# Digital_DSPv3.net
KiCad netlist of a schematic drawn in Altium Designer
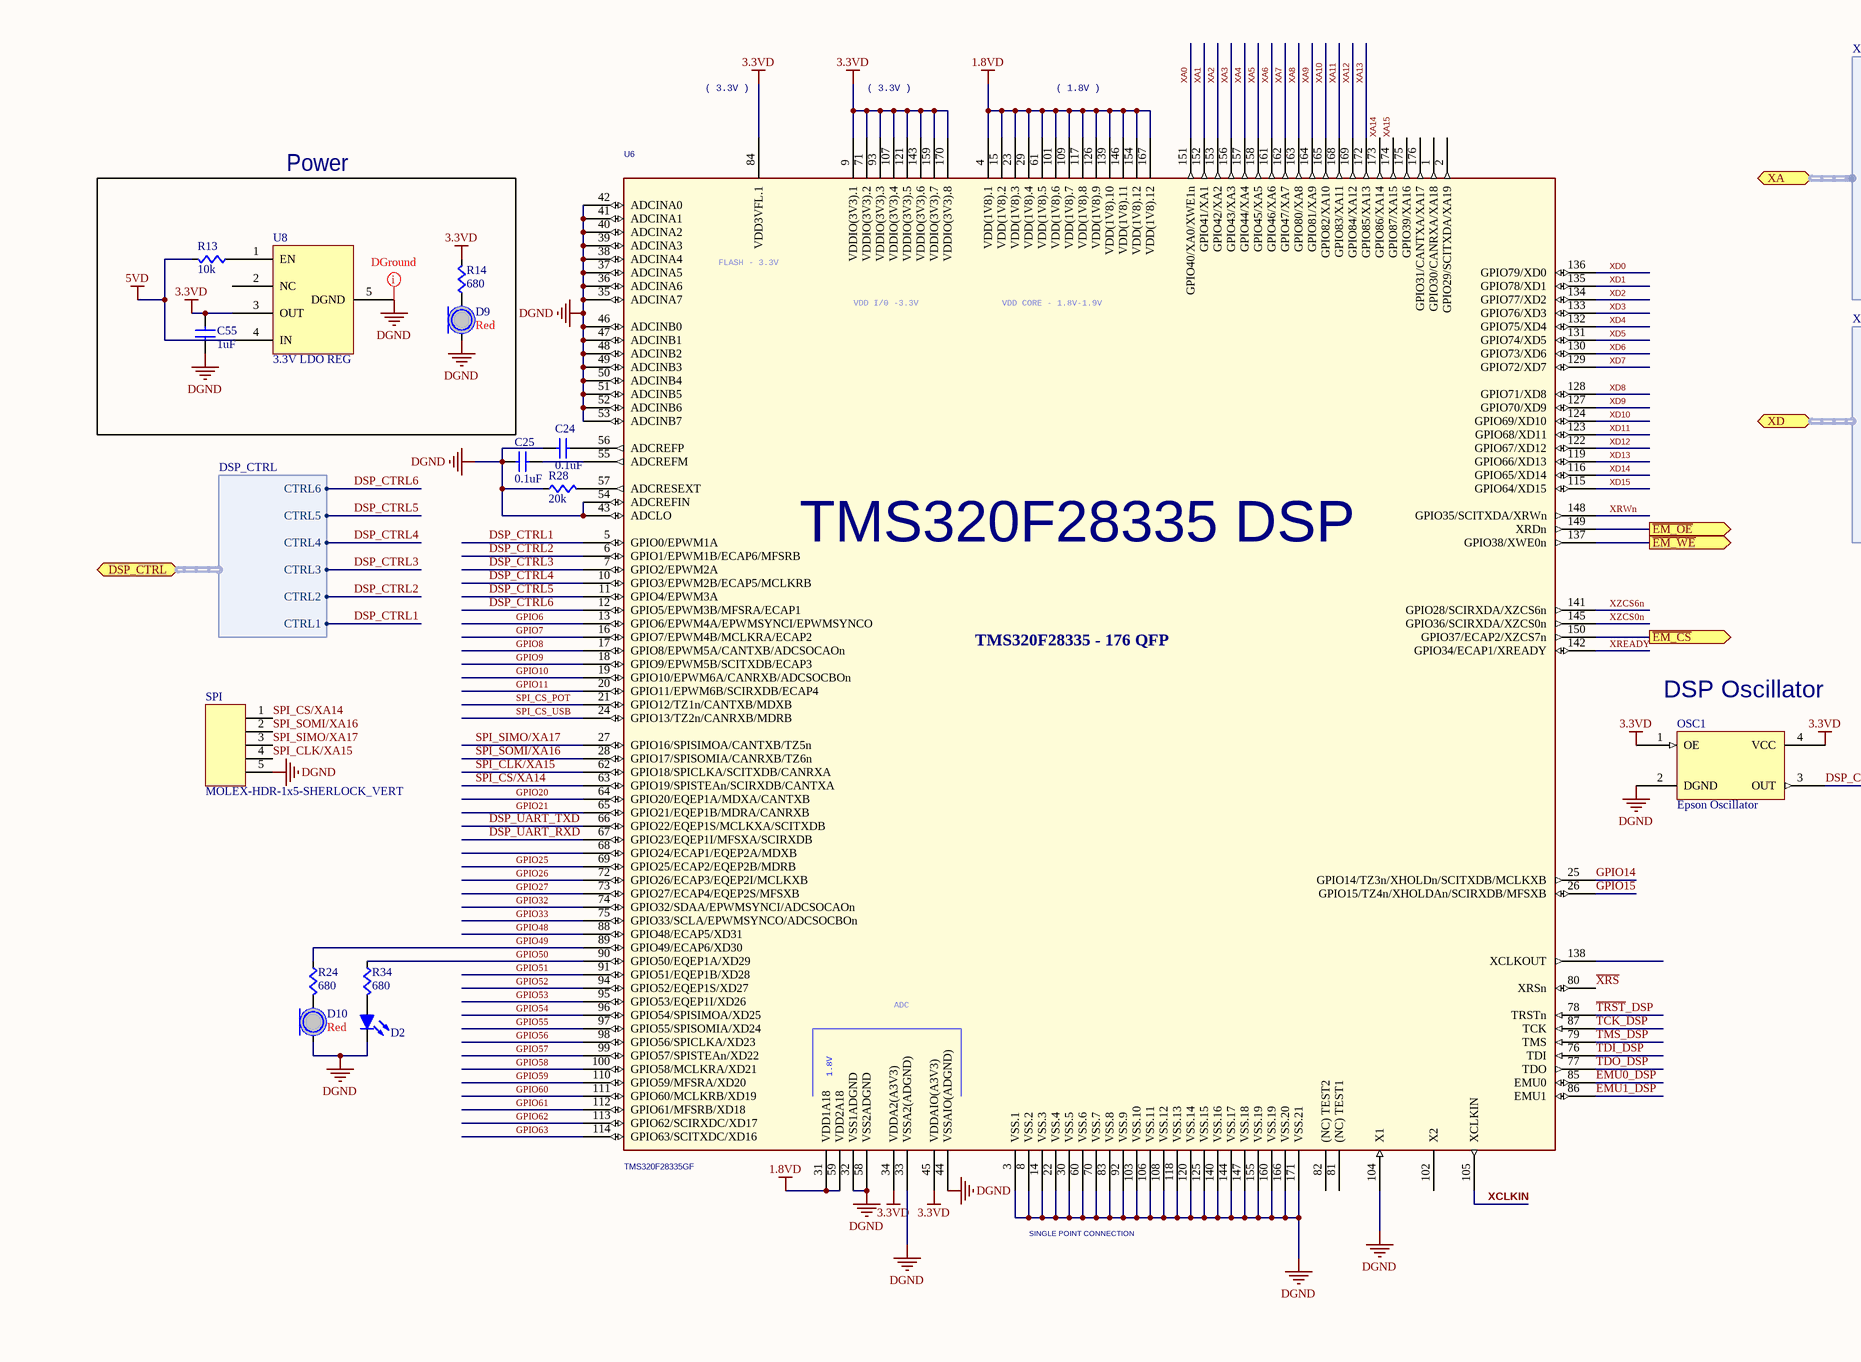
[diagram p0: Digital_DSPv3.SchDoc, top left]
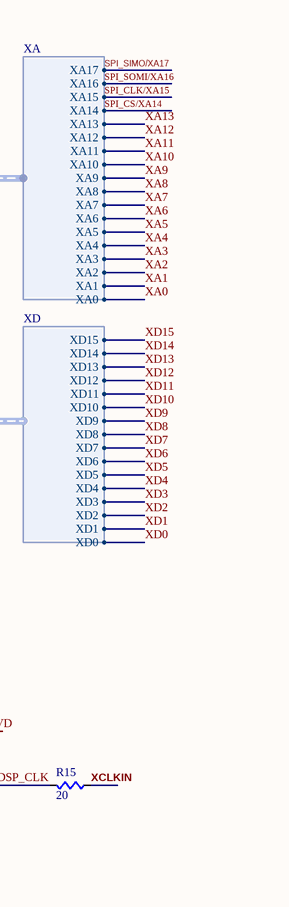
[diagram p1: Digital_DSPv3.SchDoc, top right]
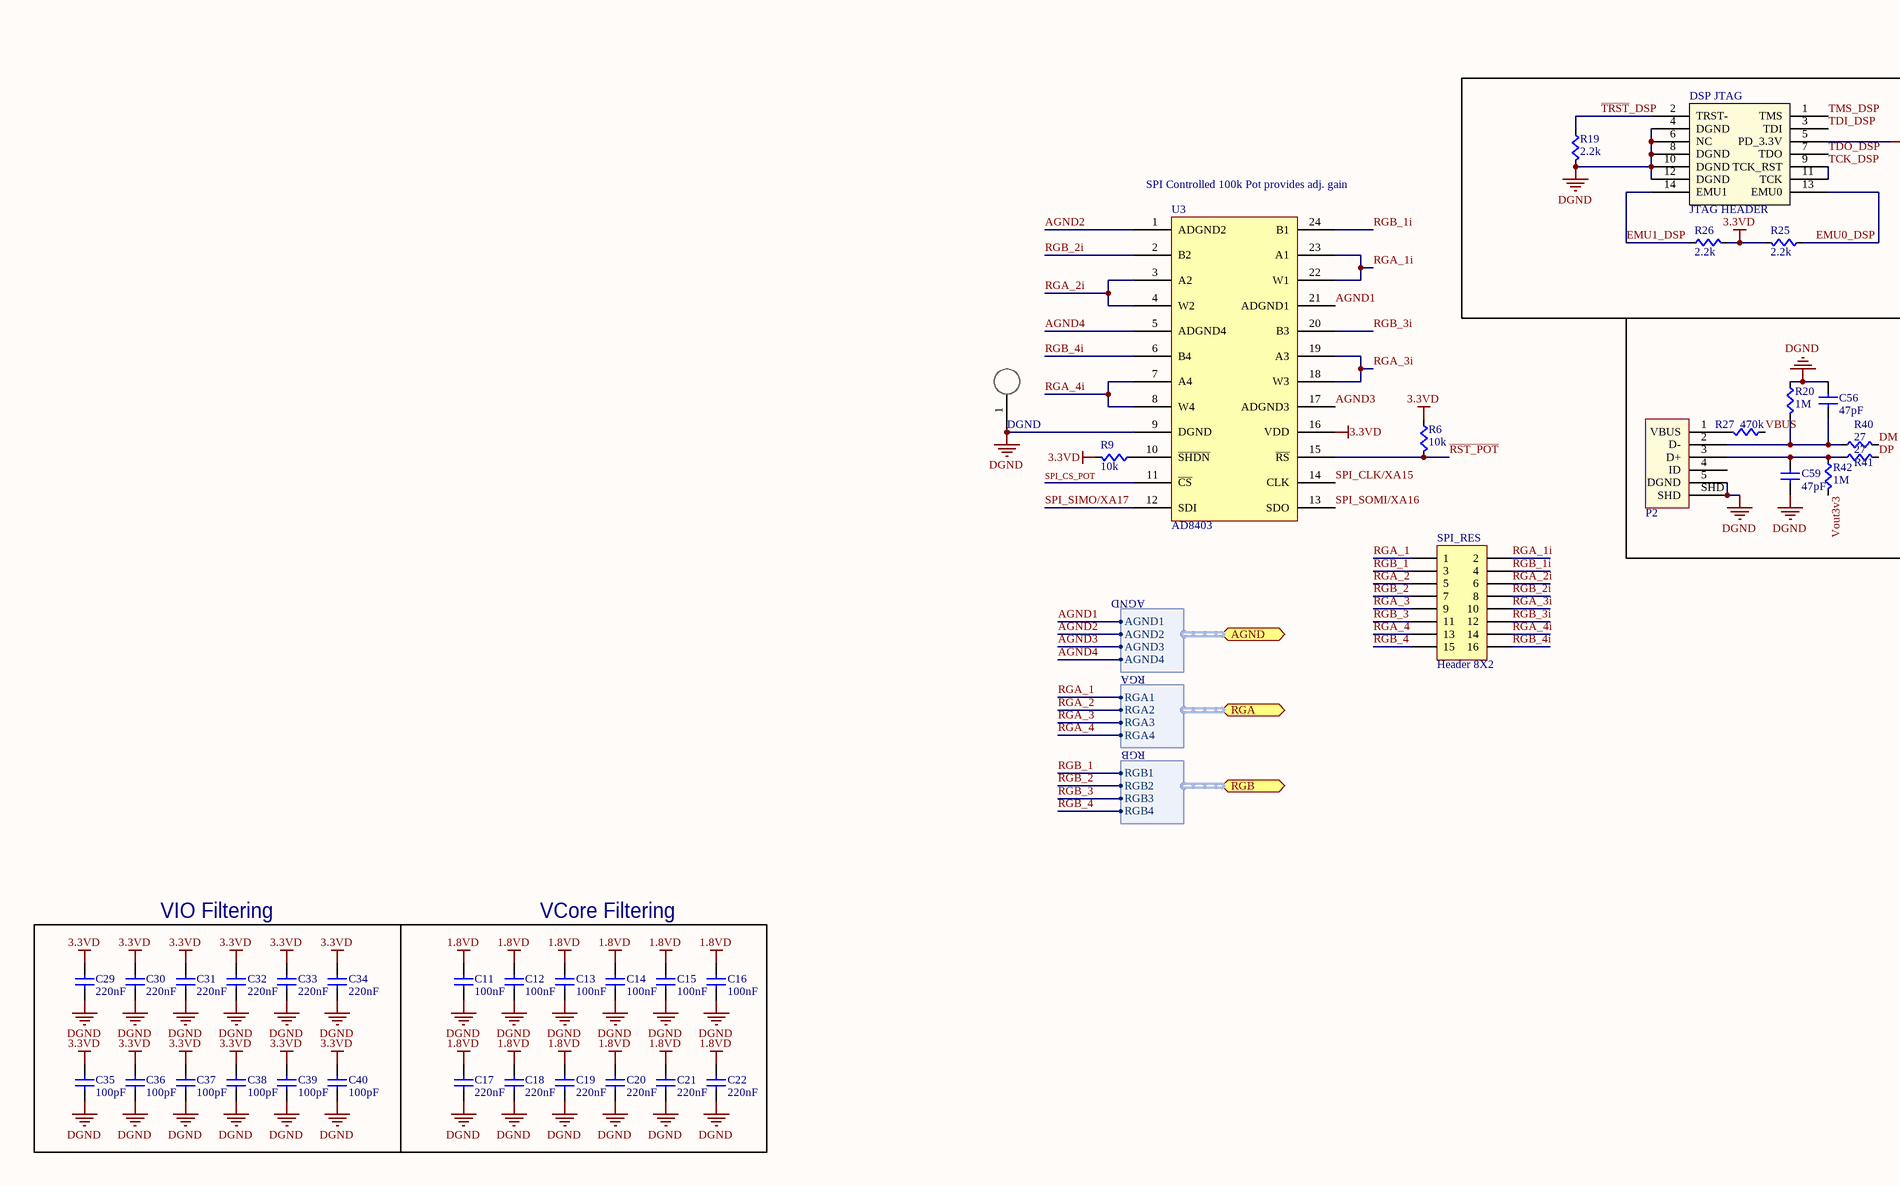
[diagram p2: Digital_DSPv3.SchDoc, bottom left]
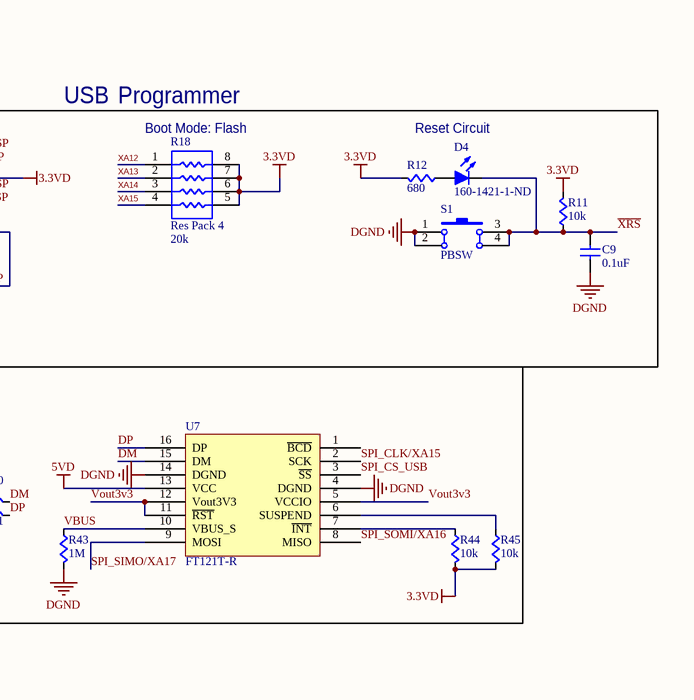
[diagram p3: Digital_DSPv3.SchDoc, bottom right]

(export (version "E")
  (design (tool "Eeschema 10.0.6"))
  (components
    (comp (ref "C9")
      (value "0.1uF")
      (footprint "CAPC0603")
      (fields (field (name "Comment") "Cap"))
      (libsource (lib "SubjuGator8") (part "Cap"))
    )
    (comp (ref "C11")
      (value "100nF")
      (footprint "CAPC0603")
      (fields (field (name "Comment") "Cap"))
      (libsource (lib "SubjuGator8") (part "Cap"))
    )
    (comp (ref "C12")
      (value "100nF")
      (footprint "CAPC0603")
      (fields (field (name "Comment") "Cap"))
      (libsource (lib "SubjuGator8") (part "Cap"))
    )
    (comp (ref "C13")
      (value "100nF")
      (footprint "CAPC0603")
      (fields (field (name "Comment") "Cap"))
      (libsource (lib "SubjuGator8") (part "Cap"))
    )
    (comp (ref "C14")
      (value "100nF")
      (footprint "CAPC0603")
      (fields (field (name "Comment") "Cap"))
      (libsource (lib "SubjuGator8") (part "Cap"))
    )
    (comp (ref "C15")
      (value "100nF")
      (footprint "CAPC0603")
      (fields (field (name "Comment") "Cap"))
      (libsource (lib "SubjuGator8") (part "Cap"))
    )
    (comp (ref "C16")
      (value "100nF")
      (footprint "CAPC0603")
      (fields (field (name "Comment") "Cap"))
      (libsource (lib "SubjuGator8") (part "Cap"))
    )
    (comp (ref "C17")
      (value "220nF")
      (footprint "CAPC0603")
      (fields (field (name "Comment") "Cap"))
      (libsource (lib "SubjuGator8") (part "Cap"))
    )
    (comp (ref "C18")
      (value "220nF")
      (footprint "CAPC0603")
      (fields (field (name "Comment") "Cap"))
      (libsource (lib "SubjuGator8") (part "Cap"))
    )
    (comp (ref "C19")
      (value "220nF")
      (footprint "CAPC0603")
      (fields (field (name "Comment") "Cap"))
      (libsource (lib "SubjuGator8") (part "Cap"))
    )
    (comp (ref "C20")
      (value "220nF")
      (footprint "CAPC0603")
      (fields (field (name "Comment") "Cap"))
      (libsource (lib "SubjuGator8") (part "Cap"))
    )
    (comp (ref "C21")
      (value "220nF")
      (footprint "CAPC0603")
      (fields (field (name "Comment") "Cap"))
      (libsource (lib "SubjuGator8") (part "Cap"))
    )
    (comp (ref "C22")
      (value "220nF")
      (footprint "CAPC0603")
      (fields (field (name "Comment") "Cap"))
      (libsource (lib "SubjuGator8") (part "Cap"))
    )
    (comp (ref "C24")
      (value "0.1uF")
      (footprint "CAPC0603")
      (description "CAP CER 1UF 50V 10% X7R 1206")
      (fields (field (name "Comment") "Cap1206"))
      (libsource (lib "Passives") (part "Cap1206"))
    )
    (comp (ref "C25")
      (value "0.1uF")
      (footprint "CAPC0603")
      (description "CAP CER 1UF 50V 10% X7R 1206")
      (fields (field (name "Comment") "Cap1206"))
      (libsource (lib "Passives") (part "Cap1206"))
    )
    (comp (ref "C29")
      (value "220nF")
      (footprint "CAPC0603")
      (fields (field (name "Comment") "Cap"))
      (libsource (lib "SubjuGator8") (part "Cap"))
    )
    (comp (ref "C30")
      (value "220nF")
      (footprint "CAPC0603")
      (fields (field (name "Comment") "Cap"))
      (libsource (lib "SubjuGator8") (part "Cap"))
    )
    (comp (ref "C31")
      (value "220nF")
      (footprint "CAPC0603")
      (fields (field (name "Comment") "Cap"))
      (libsource (lib "SubjuGator8") (part "Cap"))
    )
    (comp (ref "C32")
      (value "220nF")
      (footprint "CAPC0603")
      (fields (field (name "Comment") "Cap"))
      (libsource (lib "SubjuGator8") (part "Cap"))
    )
    (comp (ref "C33")
      (value "220nF")
      (footprint "CAPC0603")
      (fields (field (name "Comment") "Cap"))
      (libsource (lib "SubjuGator8") (part "Cap"))
    )
    (comp (ref "C34")
      (value "220nF")
      (footprint "CAPC0603")
      (fields (field (name "Comment") "Cap"))
      (libsource (lib "SubjuGator8") (part "Cap"))
    )
    (comp (ref "C35")
      (value "100pF")
      (footprint "CAPC0603")
      (fields (field (name "Comment") "Cap"))
      (libsource (lib "SubjuGator8") (part "Cap"))
    )
    (comp (ref "C36")
      (value "100pF")
      (footprint "CAPC0603")
      (fields (field (name "Comment") "Cap"))
      (libsource (lib "SubjuGator8") (part "Cap"))
    )
    (comp (ref "C37")
      (value "100pF")
      (footprint "CAPC0603")
      (fields (field (name "Comment") "Cap"))
      (libsource (lib "SubjuGator8") (part "Cap"))
    )
    (comp (ref "C38")
      (value "100pF")
      (footprint "CAPC0603")
      (fields (field (name "Comment") "Cap"))
      (libsource (lib "SubjuGator8") (part "Cap"))
    )
    (comp (ref "C39")
      (value "100pF")
      (footprint "CAPC0603")
      (fields (field (name "Comment") "Cap"))
      (libsource (lib "SubjuGator8") (part "Cap"))
    )
    (comp (ref "C40")
      (value "100pF")
      (footprint "CAPC0603")
      (fields (field (name "Comment") "Cap"))
      (libsource (lib "SubjuGator8") (part "Cap"))
    )
    (comp (ref "C55")
      (value "1uF")
      (footprint "CAPC0603")
      (description "CAP CER 1UF 50V 10% X7R 1206")
      (fields (field (name "Comment") "Cap1206"))
      (libsource (lib "Passives") (part "Cap1206"))
    )
    (comp (ref "C56")
      (value "47pF")
      (footprint "CAPC0603")
      (description "CAP CER 1UF 50V 10% X7R 1206")
      (fields (field (name "Comment") "Cap1206"))
      (libsource (lib "Passives") (part "Cap1206"))
    )
    (comp (ref "C59")
      (value "47pF")
      (footprint "CAPC0603")
      (description "CAP CER 1UF 50V 10% X7R 1206")
      (fields (field (name "Comment") "Cap1206"))
      (libsource (lib "Passives") (part "Cap1206"))
    )
    (comp (ref "D2")
      (value "LED-RED")
      (footprint "Hydrophone:LED0805-RED")
      (description "Light Emitting Diode - RED")
      (fields
        (field (name "MANUFACTURER PART NUMBER") "LTST-C171CKT")
        (field (name "MANUFACTURER") "Lite-On Inc")
      )
      (libsource (lib "Hydrophone") (part "LED-RED"))
    )
    (comp (ref "D4")
      (value "LED-RED")
      (footprint "Hydrophone:LED0805-RED")
      (description "Light Emitting Diode - RED")
      (fields
        (field (name "MANUFACTURER PART NUMBER") "LTST-C171CKT")
        (field (name "MANUFACTURER") "Lite-On Inc")
        (field (name "SUPPLIER PART NUMBER") "160-1421-1-ND")
      )
      (libsource (lib "Hydrophone") (part "LED-RED"))
    )
    (comp (ref "D9")
      (value "LED")
      (footprint "LED0805")
      (fields (field (name "COLOR") "Red"))
      (libsource (lib "SubjuGator8") (part "LED"))
    )
    (comp (ref "D10")
      (value "LED")
      (footprint "LED0805")
      (fields (field (name "COLOR") "Red"))
      (libsource (lib "SubjuGator8") (part "LED"))
    )
    (comp (ref "DGND")
      (value "Test_Point")
      (footprint "TP")
      (description "TEST POINT PC COMPACT .063\"D")
      (libsource (lib "Hydrophone") (part "Test_Point"))
    )
    (comp (ref "DSP JTAG")
      (value "JTAG HEADER")
      (footprint "Hydrophone:JTAG HEADER - 14")
      (description "14 Pin JTAG Header")
      (libsource (lib "Hydrophone") (part "JTAG-TI_14"))
    )
    (comp (ref "OSC1")
      (value "Epson Oscillator")
      (footprint "Oscillator")
      (description "15Mhz Epson Clock")
      (libsource (lib "F28335_DSC_Breakout") (part "Oscillator"))
    )
    (comp (ref "P2")
      (value "USB Micro")
      (footprint "10118192-0001LF")
      (description "USB Mini B Metal Shield SMT")
      (libsource (lib "SubjuGator8") (part "USB Micro"))
    )
    (comp (ref "R6")
      (value "10k")
      (footprint "RES0603")
      (fields (field (name "Comment") "Res"))
      (libsource (lib "SubjuGator8") (part "Res"))
    )
    (comp (ref "R9")
      (value "10k")
      (footprint "RES0603")
      (fields (field (name "Comment") "Res"))
      (libsource (lib "SubjuGator8") (part "Res"))
    )
    (comp (ref "R11")
      (value "10k")
      (footprint "RES0603")
      (fields (field (name "Comment") "Res"))
      (libsource (lib "Passives") (part "Res"))
    )
    (comp (ref "R12")
      (value "680")
      (footprint "RES0603")
      (fields (field (name "Comment") "Res"))
      (libsource (lib "SubjuGator8") (part "Res"))
    )
    (comp (ref "R13")
      (value "10k")
      (footprint "RES0603")
      (fields (field (name "Comment") "Res"))
      (libsource (lib "SubjuGator8") (part "Res"))
    )
    (comp (ref "R14")
      (value "680")
      (footprint "RES0603")
      (fields (field (name "Comment") "Res"))
      (libsource (lib "SubjuGator8") (part "Res"))
    )
    (comp (ref "R15")
      (value "20")
      (footprint "RES0603")
      (fields (field (name "Comment") "Res"))
      (libsource (lib "SubjuGator8") (part "Res"))
    )
    (comp (ref "R18")
      (value "Res Pack 4")
      (footprint "SO-8")
      (description "4 Isolated Resistor Network")
      (fields (field (name "ALTIUM_VALUE") "20k") (field (name "PUBLISHER") "Altium Limited"))
      (libsource (lib "F28335_DSC_Breakout") (part "Res Pack 4"))
    )
    (comp (ref "R19")
      (value "2.2k")
      (footprint "RES0603")
      (fields (field (name "Comment") "Res"))
      (libsource (lib "SubjuGator8") (part "Res"))
    )
    (comp (ref "R20")
      (value "1M")
      (footprint "RES0603")
      (fields (field (name "Comment") "Res"))
      (libsource (lib "SubjuGator8") (part "Res"))
    )
    (comp (ref "R24")
      (value "680")
      (footprint "RES0603")
      (fields (field (name "Comment") "Res"))
      (libsource (lib "SubjuGator8") (part "Res"))
    )
    (comp (ref "R25")
      (value "2.2k")
      (footprint "RES0603")
      (fields (field (name "Comment") "Res"))
      (libsource (lib "SubjuGator8") (part "Res"))
    )
    (comp (ref "R26")
      (value "2.2k")
      (footprint "RES0603")
      (fields (field (name "Comment") "Res"))
      (libsource (lib "SubjuGator8") (part "Res"))
    )
    (comp (ref "R27")
      (value "470k")
      (footprint "RES0603")
      (fields (field (name "Comment") "Res"))
      (libsource (lib "SubjuGator8") (part "Res"))
    )
    (comp (ref "R28")
      (value "20k")
      (footprint "RES0603")
      (fields (field (name "Comment") "Res"))
      (libsource (lib "SubjuGator8") (part "Res"))
    )
    (comp (ref "R34")
      (value "680")
      (footprint "RES0603")
      (fields (field (name "Comment") "Res"))
      (libsource (lib "SubjuGator8") (part "Res"))
    )
    (comp (ref "R40")
      (value "27")
      (footprint "RES0603")
      (fields (field (name "Comment") "Res"))
      (libsource (lib "SubjuGator8") (part "Res"))
    )
    (comp (ref "R41")
      (value "27")
      (footprint "RES0603")
      (fields (field (name "Comment") "Res"))
      (libsource (lib "SubjuGator8") (part "Res"))
    )
    (comp (ref "R42")
      (value "1M")
      (footprint "RES0603")
      (fields (field (name "Comment") "Res"))
      (libsource (lib "SubjuGator8") (part "Res"))
    )
    (comp (ref "R43")
      (value "1M")
      (footprint "RES0603")
      (fields (field (name "Comment") "Res"))
      (libsource (lib "SubjuGator8") (part "Res"))
    )
    (comp (ref "R44")
      (value "10k")
      (footprint "RES0603")
      (fields (field (name "Comment") "Res"))
      (libsource (lib "SubjuGator8") (part "Res"))
    )
    (comp (ref "R45")
      (value "10k")
      (footprint "RES0603")
      (fields (field (name "Comment") "Res"))
      (libsource (lib "SubjuGator8") (part "Res"))
    )
    (comp (ref "S1")
      (value "PBSW")
      (footprint "Hydrophone:PBSW")
      (description "Push Button Switch")
      (fields
        (field (name "MANUFACTURER") "Panasonic Electronic Components")
        (field (name "MANUFACTURER PART NUMBER") "EVQ-9P105M")
        (field (name "PUBLISHER") "Altium Limited")
      )
      (libsource (lib "Hydrophone") (part "SW-PB"))
    )
    (comp (ref "SPI")
      (value "MOLEX-HDR-1x5-SHERLOCK_VERT")
      (footprint "MOLEX-HDR-1X5-SHERLOCK-VERT")
      (libsource (lib "SubjuGator8") (part "MOLEX-HDR-1x5-SHERLOCK_VERT"))
    )
    (comp (ref "SPI_RES")
      (value "Header 8X2")
      (footprint "HDR2X8")
      (description "Header, 8-Pin, Dual row")
      (fields (field (name "PUBLISHER") "Altium Limited"))
      (libsource (lib "Miscellaneous Connectors") (part "Header 8X2"))
    )
    (comp (ref "U3")
      (value "AD8403")
      (footprint "SOIC-24n")
      (description "IC POT DGTL 8BIT 100K 4CH 24SOIC")
      (libsource (lib "SubjuGator8") (part "AD8403"))
    )
    (comp (ref "U6")
      (value "TMS320F28335GF")
      (footprint "QFP176")
      (description "Texas Instruments F28335")
      (libsource (lib "addl") (part "TMS320F283XXPGF_23"))
    )
    (comp (ref "U7")
      (value "FT121T-R")
      (footprint "TSSOP-16pin")
      (description "IC USB CONTROLLER SPI 16-TSSOP")
      (libsource (lib "SubjuGator8") (part "FT121T-R"))
    )
    (comp (ref "U8")
      (value "3.3V LDO REG")
      (footprint "SOT223-8N")
      (description "IC REG LDO 3.3V 0.5A SOT223-5")
      (libsource (lib "SubjuGator8") (part "LP38691"))
    )
  )
  (nets
    (net (code "7") (name "/AGND1") (class "Default")
      (node (ref "U3") (pin "21") (pinfunction "ADGND1_21") (pintype "passive"))
    )
    (net (code "8") (name "/AGND2") (class "Default")
      (node (ref "U3") (pin "1") (pinfunction "ADGND2_1") (pintype "passive"))
    )
    (net (code "9") (name "/AGND3") (class "Default")
      (node (ref "U3") (pin "17") (pinfunction "ADGND3_17") (pintype "passive"))
    )
    (net (code "10") (name "/AGND4") (class "Default")
      (node (ref "U3") (pin "5") (pinfunction "ADGND4_5") (pintype "passive"))
    )
    (net (code "11") (name "/DM") (class "Default")
      (node (ref "R40") (pin "1") (pinfunction "A_1") (pintype "passive"))
      (node (ref "U7") (pin "15") (pinfunction "DM_15") (pintype "passive"))
    )
    (net (code "12") (name "/DP") (class "Default")
      (node (ref "R41") (pin "1") (pinfunction "A_1") (pintype "passive"))
      (node (ref "U7") (pin "16") (pinfunction "DP_16") (pintype "passive"))
    )
    (net (code "13") (name "/DSP_CLK") (class "Default")
      (node (ref "OSC1") (pin "3") (pinfunction "OUT_3") (pintype "output"))
      (node (ref "R15") (pin "1") (pinfunction "A_1") (pintype "passive"))
    )
    (net (code "14") (name "/DSP_CTRL1") (class "Default")
      (node (ref "U6") (pin "5") (pinfunction "GPIO0/EPWM1A_5") (pintype "bidirectional"))
    )
    (net (code "15") (name "/DSP_CTRL2") (class "Default")
      (node (ref "U6") (pin "6") (pinfunction "GPIO1/EPWM1B/ECAP6/MFSRB_6") (pintype "bidirectional"))
    )
    (net (code "16") (name "/DSP_CTRL3") (class "Default")
      (node (ref "U6") (pin "7") (pinfunction "GPIO2/EPWM2A_7") (pintype "bidirectional"))
    )
    (net (code "17") (name "/DSP_CTRL4") (class "Default")
      (node (ref "U6") (pin "10") (pinfunction "GPIO3/EPWM2B/ECAP5/MCLKRB_10") (pintype "bidirectional"))
    )
    (net (code "18") (name "/DSP_CTRL5") (class "Default")
      (node (ref "U6") (pin "11") (pinfunction "GPIO4/EPWM3A_11") (pintype "bidirectional"))
    )
    (net (code "19") (name "/DSP_CTRL6") (class "Default")
      (node (ref "U6") (pin "12") (pinfunction "GPIO5/EPWM3B/MFSRA/ECAP1_12") (pintype "bidirectional"))
    )
    (net (code "20") (name "/DSP_UART_RXD") (class "Default")
      (node (ref "U6") (pin "67") (pinfunction "GPIO23/EQEP1I/MFSXA/SCIRXDB_67") (pintype "bidirectional"))
    )
    (net (code "21") (name "/DSP_UART_TXD") (class "Default")
      (node (ref "U6") (pin "66") (pinfunction "GPIO22/EQEP1S/MCLKXA/SCITXDB_66") (pintype "bidirectional"))
    )
    (net (code "22") (name "/EMU0_DSP") (class "Default")
      (node (ref "DSP JTAG") (pin "13") (pinfunction "EMU0_13") (pintype "passive"))
      (node (ref "R25") (pin "2") (pinfunction "B_2") (pintype "passive"))
      (node (ref "U6") (pin "85") (pinfunction "EMU0_85") (pintype "bidirectional"))
    )
    (net (code "23") (name "/EMU1_DSP") (class "Default")
      (node (ref "DSP JTAG") (pin "14") (pinfunction "EMU1_14") (pintype "passive"))
      (node (ref "R26") (pin "2") (pinfunction "B_2") (pintype "passive"))
      (node (ref "U6") (pin "86") (pinfunction "EMU1_86") (pintype "bidirectional"))
    )
    (net (code "24") (name "/GPIO6") (class "Default")
      (node (ref "U6") (pin "13") (pinfunction "GPIO6/EPWM4A/EPWMSYNCI/EPWMSYNCO_13") (pintype "bidirectional"))
    )
    (net (code "25") (name "/GPIO7") (class "Default")
      (node (ref "U6") (pin "16") (pinfunction "GPIO7/EPWM4B/MCLKRA/ECAP2_16") (pintype "bidirectional"))
    )
    (net (code "26") (name "/GPIO8") (class "Default")
      (node (ref "U6") (pin "17") (pinfunction "GPIO8/EPWM5A/CANTXB/ADCSOCAOn_17") (pintype "bidirectional"))
    )
    (net (code "27") (name "/GPIO9") (class "Default")
      (node (ref "U6") (pin "18") (pinfunction "GPIO9/EPWM5B/SCITXDB/ECAP3_18") (pintype "bidirectional"))
    )
    (net (code "28") (name "/GPIO10") (class "Default")
      (node (ref "U6") (pin "19") (pinfunction "GPIO10/EPWM6A/CANRXB/ADCSOCBOn_19") (pintype "bidirectional"))
    )
    (net (code "29") (name "/GPIO11") (class "Default")
      (node (ref "U6") (pin "20") (pinfunction "GPIO11/EPWM6B/SCIRXDB/ECAP4_20") (pintype "bidirectional"))
    )
    (net (code "30") (name "/GPIO14") (class "Default")
      (node (ref "U6") (pin "25") (pinfunction "GPIO14/TZ3n/XHOLDn/SCITXDB/MCLKXB_25") (pintype "output"))
    )
    (net (code "31") (name "/GPIO15") (class "Default")
      (node (ref "U6") (pin "26") (pinfunction "GPIO15/TZ4n/XHOLDAn/SCIRXDB/MFSXB_26") (pintype "bidirectional"))
    )
    (net (code "32") (name "/GPIO20") (class "Default")
      (node (ref "U6") (pin "64") (pinfunction "GPIO20/EQEP1A/MDXA/CANTXB_64") (pintype "bidirectional"))
    )
    (net (code "33") (name "/GPIO21") (class "Default")
      (node (ref "U6") (pin "65") (pinfunction "GPIO21/EQEP1B/MDRA/CANRXB_65") (pintype "bidirectional"))
    )
    (net (code "34") (name "/GPIO25") (class "Default")
      (node (ref "U6") (pin "69") (pinfunction "GPIO25/ECAP2/EQEP2B/MDRB_69") (pintype "bidirectional"))
    )
    (net (code "35") (name "/GPIO26") (class "Default")
      (node (ref "U6") (pin "72") (pinfunction "GPIO26/ECAP3/EQEP2I/MCLKXB_72") (pintype "bidirectional"))
    )
    (net (code "36") (name "/GPIO27") (class "Default")
      (node (ref "U6") (pin "73") (pinfunction "GPIO27/ECAP4/EQEP2S/MFSXB_73") (pintype "bidirectional"))
    )
    (net (code "37") (name "/GPIO32") (class "Default")
      (node (ref "U6") (pin "74") (pinfunction "GPIO32/SDAA/EPWMSYNCI/ADCSOCAOn_74") (pintype "bidirectional"))
    )
    (net (code "38") (name "/GPIO33") (class "Default")
      (node (ref "U6") (pin "75") (pinfunction "GPIO33/SCLA/EPWMSYNCO/ADCSOCBOn_75") (pintype "bidirectional"))
    )
    (net (code "39") (name "/GPIO48") (class "Default")
      (node (ref "U6") (pin "88") (pinfunction "GPIO48/ECAP5/XD31_88") (pintype "bidirectional"))
    )
    (net (code "40") (name "/GPIO49") (class "Default")
      (node (ref "R24") (pin "2") (pinfunction "B_2") (pintype "passive"))
      (node (ref "U6") (pin "89") (pinfunction "GPIO49/ECAP6/XD30_89") (pintype "bidirectional"))
    )
    (net (code "41") (name "/GPIO50") (class "Default")
      (node (ref "R34") (pin "2") (pinfunction "B_2") (pintype "passive"))
      (node (ref "U6") (pin "90") (pinfunction "GPIO50/EQEP1A/XD29_90") (pintype "bidirectional"))
    )
    (net (code "42") (name "/GPIO51") (class "Default")
      (node (ref "U6") (pin "91") (pinfunction "GPIO51/EQEP1B/XD28_91") (pintype "bidirectional"))
    )
    (net (code "43") (name "/GPIO52") (class "Default")
      (node (ref "U6") (pin "94") (pinfunction "GPIO52/EQEP1S/XD27_94") (pintype "bidirectional"))
    )
    (net (code "44") (name "/GPIO53") (class "Default")
      (node (ref "U6") (pin "95") (pinfunction "GPIO53/EQEP1I/XD26_95") (pintype "bidirectional"))
    )
    (net (code "45") (name "/GPIO54") (class "Default")
      (node (ref "U6") (pin "96") (pinfunction "GPIO54/SPISIMOA/XD25_96") (pintype "bidirectional"))
    )
    (net (code "46") (name "/GPIO55") (class "Default")
      (node (ref "U6") (pin "97") (pinfunction "GPIO55/SPISOMIA/XD24_97") (pintype "bidirectional"))
    )
    (net (code "47") (name "/GPIO56") (class "Default")
      (node (ref "U6") (pin "98") (pinfunction "GPIO56/SPICLKA/XD23_98") (pintype "bidirectional"))
    )
    (net (code "48") (name "/GPIO57") (class "Default")
      (node (ref "U6") (pin "99") (pinfunction "GPIO57/SPISTEAn/XD22_99") (pintype "bidirectional"))
    )
    (net (code "49") (name "/GPIO58") (class "Default")
      (node (ref "U6") (pin "100") (pinfunction "GPIO58/MCLKRA/XD21_100") (pintype "bidirectional"))
    )
    (net (code "50") (name "/GPIO59") (class "Default")
      (node (ref "U6") (pin "110") (pinfunction "GPIO59/MFSRA/XD20_110") (pintype "bidirectional"))
    )
    (net (code "51") (name "/GPIO60") (class "Default")
      (node (ref "U6") (pin "111") (pinfunction "GPIO60/MCLKRB/XD19_111") (pintype "bidirectional"))
    )
    (net (code "52") (name "/GPIO61") (class "Default")
      (node (ref "U6") (pin "112") (pinfunction "GPIO61/MFSRB/XD18_112") (pintype "bidirectional"))
    )
    (net (code "53") (name "/GPIO62") (class "Default")
      (node (ref "U6") (pin "113") (pinfunction "GPIO62/SCIRXDC/XD17_113") (pintype "bidirectional"))
    )
    (net (code "54") (name "/GPIO63") (class "Default")
      (node (ref "U6") (pin "114") (pinfunction "GPIO63/SCITXDC/XD16_114") (pintype "bidirectional"))
    )
    (net (code "55") (name "/RGA_1") (class "Default")
      (node (ref "SPI_RES") (pin "1") (pinfunction "1_1") (pintype "passive"))
    )
    (net (code "56") (name "/RGA_1i") (class "Default")
      (node (ref "SPI_RES") (pin "2") (pinfunction "2_2") (pintype "passive"))
      (node (ref "U3") (pin "22") (pinfunction "W1_22") (pintype "passive"))
      (node (ref "U3") (pin "23") (pinfunction "A1_23") (pintype "passive"))
    )
    (net (code "57") (name "/RGA_2") (class "Default")
      (node (ref "SPI_RES") (pin "5") (pinfunction "5_5") (pintype "passive"))
    )
    (net (code "58") (name "/RGA_2i") (class "Default")
      (node (ref "SPI_RES") (pin "6") (pinfunction "6_6") (pintype "passive"))
      (node (ref "U3") (pin "3") (pinfunction "A2_3") (pintype "passive"))
      (node (ref "U3") (pin "4") (pinfunction "W2_4") (pintype "passive"))
    )
    (net (code "59") (name "/RGA_3") (class "Default")
      (node (ref "SPI_RES") (pin "9") (pinfunction "9_9") (pintype "passive"))
    )
    (net (code "60") (name "/RGA_3i") (class "Default")
      (node (ref "SPI_RES") (pin "10") (pinfunction "10_10") (pintype "passive"))
      (node (ref "U3") (pin "18") (pinfunction "W3_18") (pintype "passive"))
      (node (ref "U3") (pin "19") (pinfunction "A3_19") (pintype "passive"))
    )
    (net (code "61") (name "/RGA_4") (class "Default")
      (node (ref "SPI_RES") (pin "13") (pinfunction "13_13") (pintype "passive"))
    )
    (net (code "62") (name "/RGA_4i") (class "Default")
      (node (ref "SPI_RES") (pin "14") (pinfunction "14_14") (pintype "passive"))
      (node (ref "U3") (pin "7") (pinfunction "A4_7") (pintype "passive"))
      (node (ref "U3") (pin "8") (pinfunction "W4_8") (pintype "passive"))
    )
    (net (code "63") (name "/RGB_1") (class "Default")
      (node (ref "SPI_RES") (pin "3") (pinfunction "3_3") (pintype "passive"))
    )
    (net (code "64") (name "/RGB_1i") (class "Default")
      (node (ref "SPI_RES") (pin "4") (pinfunction "4_4") (pintype "passive"))
      (node (ref "U3") (pin "24") (pinfunction "B1_24") (pintype "passive"))
    )
    (net (code "65") (name "/RGB_2") (class "Default")
      (node (ref "SPI_RES") (pin "7") (pinfunction "7_7") (pintype "passive"))
    )
    (net (code "66") (name "/RGB_2i") (class "Default")
      (node (ref "SPI_RES") (pin "8") (pinfunction "8_8") (pintype "passive"))
      (node (ref "U3") (pin "2") (pinfunction "B2_2") (pintype "passive"))
    )
    (net (code "67") (name "/RGB_3") (class "Default")
      (node (ref "SPI_RES") (pin "11") (pinfunction "11_11") (pintype "passive"))
    )
    (net (code "68") (name "/RGB_3i") (class "Default")
      (node (ref "SPI_RES") (pin "12") (pinfunction "12_12") (pintype "passive"))
      (node (ref "U3") (pin "20") (pinfunction "B3_20") (pintype "passive"))
    )
    (net (code "69") (name "/RGB_4") (class "Default")
      (node (ref "SPI_RES") (pin "15") (pinfunction "15_15") (pintype "passive"))
    )
    (net (code "70") (name "/RGB_4i") (class "Default")
      (node (ref "SPI_RES") (pin "16") (pinfunction "16_16") (pintype "passive"))
      (node (ref "U3") (pin "6") (pinfunction "B4_6") (pintype "passive"))
    )
    (net (code "71") (name "/SPI_CLK{slash}XA15") (class "Default")
      (node (ref "SPI") (pin "4") (pinfunction "4_4") (pintype "passive"))
      (node (ref "U3") (pin "14") (pinfunction "CLK_14") (pintype "passive"))
      (node (ref "U6") (pin "62") (pinfunction "GPIO18/SPICLKA/SCITXDB/CANRXA_62") (pintype "bidirectional"))
      (node (ref "U7") (pin "2") (pinfunction "SCK_2") (pintype "passive"))
    )
    (net (code "72") (name "/SPI_CS_POT") (class "Default")
      (node (ref "U3") (pin "11") (pinfunction "~{CS}_11") (pintype "passive"))
      (node (ref "U6") (pin "21") (pinfunction "GPIO12/TZ1n/CANTXB/MDXB_21") (pintype "bidirectional"))
    )
    (net (code "73") (name "/SPI_CS_USB") (class "Default")
      (node (ref "U6") (pin "24") (pinfunction "GPIO13/TZ2n/CANRXB/MDRB_24") (pintype "bidirectional"))
      (node (ref "U7") (pin "3") (pinfunction "~{SS}_3") (pintype "passive"))
    )
    (net (code "74") (name "/SPI_CS{slash}XA14") (class "Default")
      (node (ref "SPI") (pin "1") (pinfunction "1_1") (pintype "passive"))
      (node (ref "U6") (pin "63") (pinfunction "GPIO19/SPISTEAn/SCIRXDB/CANTXA_63") (pintype "bidirectional"))
    )
    (net (code "75") (name "/SPI_SIMO{slash}XA17") (class "Default")
      (node (ref "SPI") (pin "3") (pinfunction "3_3") (pintype "passive"))
      (node (ref "U3") (pin "12") (pinfunction "SDI_12") (pintype "passive"))
      (node (ref "U6") (pin "27") (pinfunction "GPIO16/SPISIMOA/CANTXB/TZ5n_27") (pintype "bidirectional"))
      (node (ref "U7") (pin "9") (pinfunction "MOSI_9") (pintype "passive"))
    )
    (net (code "76") (name "/SPI_SOMI{slash}XA16") (class "Default")
      (node (ref "SPI") (pin "2") (pinfunction "2_2") (pintype "passive"))
      (node (ref "U3") (pin "13") (pinfunction "SDO_13") (pintype "passive"))
      (node (ref "U6") (pin "28") (pinfunction "GPIO17/SPISOMIA/CANRXB/TZ6n_28") (pintype "bidirectional"))
      (node (ref "U7") (pin "8") (pinfunction "MISO_8") (pintype "passive"))
    )
    (net (code "77") (name "/TCK_DSP") (class "Default")
      (node (ref "DSP JTAG") (pin "11") (pinfunction "TCK_11") (pintype "passive"))
      (node (ref "DSP JTAG") (pin "9") (pinfunction "TCK_RST_9") (pintype "passive"))
      (node (ref "U6") (pin "87") (pinfunction "TCK_87") (pintype "input"))
    )
    (net (code "78") (name "/TDI_DSP") (class "Default")
      (node (ref "DSP JTAG") (pin "3") (pinfunction "TDI_3") (pintype "passive"))
      (node (ref "U6") (pin "76") (pinfunction "TDI_76") (pintype "input"))
    )
    (net (code "79") (name "/TDO_DSP") (class "Default")
      (node (ref "DSP JTAG") (pin "7") (pinfunction "TDO_7") (pintype "passive"))
      (node (ref "U6") (pin "77") (pinfunction "TDO_77") (pintype "output"))
    )
    (net (code "80") (name "/TMS_DSP") (class "Default")
      (node (ref "DSP JTAG") (pin "1") (pinfunction "TMS_1") (pintype "passive"))
      (node (ref "U6") (pin "79") (pinfunction "TMS_79") (pintype "input"))
    )
    (net (code "81") (name "/VBUS") (class "Default")
      (node (ref "R27") (pin "2") (pinfunction "B_2") (pintype "passive"))
      (node (ref "R43") (pin "2") (pinfunction "B_2") (pintype "passive"))
      (node (ref "U7") (pin "10") (pinfunction "VBUS_S_10") (pintype "passive"))
    )
    (net (code "82") (name "/Vout3v3") (class "Default")
      (node (ref "R42") (pin "1") (pinfunction "A_1") (pintype "passive"))
      (node (ref "U7") (pin "11") (pinfunction "~{RST}_11") (pintype "passive"))
      (node (ref "U7") (pin "12") (pinfunction "Vout3V3_12") (pintype "passive"))
      (node (ref "U7") (pin "5") (pinfunction "VCCIO_5") (pintype "passive"))
    )
    (net (code "83") (name "/XA0") (class "Default")
      (node (ref "U6") (pin "151") (pinfunction "GPIO40/XA0/XWE1n_151") (pintype "output"))
    )
    (net (code "84") (name "/XA1") (class "Default")
      (node (ref "U6") (pin "152") (pinfunction "GPIO41/XA1_152") (pintype "output"))
    )
    (net (code "85") (name "/XA2") (class "Default")
      (node (ref "U6") (pin "153") (pinfunction "GPIO42/XA2_153") (pintype "output"))
    )
    (net (code "86") (name "/XA3") (class "Default")
      (node (ref "U6") (pin "156") (pinfunction "GPIO43/XA3_156") (pintype "output"))
    )
    (net (code "87") (name "/XA4") (class "Default")
      (node (ref "U6") (pin "157") (pinfunction "GPIO44/XA4_157") (pintype "output"))
    )
    (net (code "88") (name "/XA5") (class "Default")
      (node (ref "U6") (pin "158") (pinfunction "GPIO45/XA5_158") (pintype "output"))
    )
    (net (code "89") (name "/XA6") (class "Default")
      (node (ref "U6") (pin "161") (pinfunction "GPIO46/XA6_161") (pintype "output"))
    )
    (net (code "90") (name "/XA7") (class "Default")
      (node (ref "U6") (pin "162") (pinfunction "GPIO47/XA7_162") (pintype "output"))
    )
    (net (code "91") (name "/XA8") (class "Default")
      (node (ref "U6") (pin "163") (pinfunction "GPIO80/XA8_163") (pintype "output"))
    )
    (net (code "92") (name "/XA9") (class "Default")
      (node (ref "U6") (pin "164") (pinfunction "GPIO81/XA9_164") (pintype "output"))
    )
    (net (code "93") (name "/XA10") (class "Default")
      (node (ref "U6") (pin "165") (pinfunction "GPIO82/XA10_165") (pintype "output"))
    )
    (net (code "94") (name "/XA11") (class "Default")
      (node (ref "U6") (pin "168") (pinfunction "GPIO83/XA11_168") (pintype "output"))
    )
    (net (code "95") (name "/XA12") (class "Default")
      (node (ref "R18") (pin "1") (pinfunction "1_1") (pintype "passive"))
      (node (ref "U6") (pin "169") (pinfunction "GPIO84/XA12_169") (pintype "output"))
    )
    (net (code "96") (name "/XA13") (class "Default")
      (node (ref "R18") (pin "2") (pinfunction "2_2") (pintype "passive"))
      (node (ref "U6") (pin "172") (pinfunction "GPIO85/XA13_172") (pintype "output"))
    )
    (net (code "97") (name "/XA14") (class "Default")
      (node (ref "R18") (pin "3") (pinfunction "3_3") (pintype "passive"))
      (node (ref "U6") (pin "173") (pinfunction "GPIO86/XA14_173") (pintype "output"))
    )
    (net (code "98") (name "/XA15") (class "Default")
      (node (ref "R18") (pin "4") (pinfunction "4_4") (pintype "passive"))
      (node (ref "U6") (pin "174") (pinfunction "GPIO87/XA15_174") (pintype "output"))
    )
    (net (code "99") (name "/XCLKIN") (class "Default")
      (node (ref "R15") (pin "2") (pinfunction "B_2") (pintype "passive"))
      (node (ref "U6") (pin "105") (pinfunction "XCLKIN_105") (pintype "output"))
    )
    (net (code "100") (name "/XD0") (class "Default")
      (node (ref "U6") (pin "136") (pinfunction "GPIO79/XD0_136") (pintype "bidirectional"))
    )
    (net (code "101") (name "/XD1") (class "Default")
      (node (ref "U6") (pin "135") (pinfunction "GPIO78/XD1_135") (pintype "bidirectional"))
    )
    (net (code "102") (name "/XD2") (class "Default")
      (node (ref "U6") (pin "134") (pinfunction "GPIO77/XD2_134") (pintype "bidirectional"))
    )
    (net (code "103") (name "/XD3") (class "Default")
      (node (ref "U6") (pin "133") (pinfunction "GPIO76/XD3_133") (pintype "bidirectional"))
    )
    (net (code "104") (name "/XD4") (class "Default")
      (node (ref "U6") (pin "132") (pinfunction "GPIO75/XD4_132") (pintype "bidirectional"))
    )
    (net (code "105") (name "/XD5") (class "Default")
      (node (ref "U6") (pin "131") (pinfunction "GPIO74/XD5_131") (pintype "bidirectional"))
    )
    (net (code "106") (name "/XD6") (class "Default")
      (node (ref "U6") (pin "130") (pinfunction "GPIO73/XD6_130") (pintype "bidirectional"))
    )
    (net (code "107") (name "/XD7") (class "Default")
      (node (ref "U6") (pin "129") (pinfunction "GPIO72/XD7_129") (pintype "bidirectional"))
    )
    (net (code "108") (name "/XD8") (class "Default")
      (node (ref "U6") (pin "128") (pinfunction "GPIO71/XD8_128") (pintype "bidirectional"))
    )
    (net (code "109") (name "/XD9") (class "Default")
      (node (ref "U6") (pin "127") (pinfunction "GPIO70/XD9_127") (pintype "bidirectional"))
    )
    (net (code "110") (name "/XD10") (class "Default")
      (node (ref "U6") (pin "124") (pinfunction "GPIO69/XD10_124") (pintype "bidirectional"))
    )
    (net (code "111") (name "/XD11") (class "Default")
      (node (ref "U6") (pin "123") (pinfunction "GPIO68/XD11_123") (pintype "bidirectional"))
    )
    (net (code "112") (name "/XD12") (class "Default")
      (node (ref "U6") (pin "122") (pinfunction "GPIO67/XD12_122") (pintype "bidirectional"))
    )
    (net (code "113") (name "/XD13") (class "Default")
      (node (ref "U6") (pin "119") (pinfunction "GPIO66/XD13_119") (pintype "bidirectional"))
    )
    (net (code "114") (name "/XD14") (class "Default")
      (node (ref "U6") (pin "116") (pinfunction "GPIO65/XD14_116") (pintype "bidirectional"))
    )
    (net (code "115") (name "/XD15") (class "Default")
      (node (ref "U6") (pin "115") (pinfunction "GPIO64/XD15_115") (pintype "bidirectional"))
    )
    (net (code "116") (name "/XREADY") (class "Default")
      (node (ref "U6") (pin "142") (pinfunction "GPIO34/ECAP1/XREADY_142") (pintype "bidirectional"))
    )
    (net (code "117") (name "/XRWn") (class "Default")
      (node (ref "U6") (pin "148") (pinfunction "GPIO35/SCITXDA/XRWn_148") (pintype "output"))
    )
    (net (code "118") (name "/XZCS0n") (class "Default")
      (node (ref "U6") (pin "145") (pinfunction "GPIO36/SCIRXDA/XZCS0n_145") (pintype "output"))
    )
    (net (code "119") (name "/XZCS6n") (class "Default")
      (node (ref "U6") (pin "141") (pinfunction "GPIO28/SCIRXDA/XZCS6n_141") (pintype "output"))
    )
    (net (code "126") (name "/~{EM_CS}") (class "Default")
      (node (ref "U6") (pin "150") (pinfunction "GPIO37/ECAP2/XZCS7n_150") (pintype "output"))
    )
    (net (code "127") (name "/~{EM_OE}") (class "Default")
      (node (ref "U6") (pin "149") (pinfunction "XRDn_149") (pintype "output"))
    )
    (net (code "128") (name "/~{EM_WE}") (class "Default")
      (node (ref "U6") (pin "137") (pinfunction "GPIO38/XWE0n_137") (pintype "output"))
    )
    (net (code "129") (name "/~{RST_POT}") (class "Default")
      (node (ref "R6") (pin "1") (pinfunction "A_1") (pintype "passive"))
      (node (ref "U3") (pin "15") (pinfunction "~{RS}_15") (pintype "passive"))
    )
    (net (code "130") (name "/~{TRST}_DSP") (class "Default")
      (node (ref "DSP JTAG") (pin "2") (pinfunction "TRST-_2") (pintype "passive"))
      (node (ref "R19") (pin "2") (pinfunction "B_2") (pintype "passive"))
      (node (ref "U6") (pin "78") (pinfunction "TRSTn_78") (pintype "input"))
    )
    (net (code "131") (name "/~{XRS}") (class "Default")
      (node (ref "C9") (pin "1") (pinfunction "A_1") (pintype "passive"))
      (node (ref "D4") (pin "1") (pinfunction "K_1") (pintype "passive"))
      (node (ref "R11") (pin "2") (pinfunction "B_2") (pintype "passive"))
      (node (ref "S1") (pin "3") (pinfunction "B_3") (pintype "passive"))
      (node (ref "S1") (pin "4") (pinfunction "B'_4") (pintype "passive"))
      (node (ref "U6") (pin "80") (pinfunction "XRSn_80") (pintype "bidirectional"))
    )
    (net (code "132") (name "1.8VD") (class "Default")
      (node (ref "C11") (pin "1") (pinfunction "A_1") (pintype "passive"))
      (node (ref "C12") (pin "1") (pinfunction "A_1") (pintype "passive"))
      (node (ref "C13") (pin "1") (pinfunction "A_1") (pintype "passive"))
      (node (ref "C14") (pin "1") (pinfunction "A_1") (pintype "passive"))
      (node (ref "C15") (pin "1") (pinfunction "A_1") (pintype "passive"))
      (node (ref "C16") (pin "1") (pinfunction "A_1") (pintype "passive"))
      (node (ref "C17") (pin "1") (pinfunction "A_1") (pintype "passive"))
      (node (ref "C18") (pin "1") (pinfunction "A_1") (pintype "passive"))
      (node (ref "C19") (pin "1") (pinfunction "A_1") (pintype "passive"))
      (node (ref "C20") (pin "1") (pinfunction "A_1") (pintype "passive"))
      (node (ref "C21") (pin "1") (pinfunction "A_1") (pintype "passive"))
      (node (ref "C22") (pin "1") (pinfunction "A_1") (pintype "passive"))
      (node (ref "U6") (pin "101") (pinfunction "VDD(1V8).6_101") (pintype "power_in"))
      (node (ref "U6") (pin "109") (pinfunction "VDD(1V8).7_109") (pintype "power_in"))
      (node (ref "U6") (pin "117") (pinfunction "VDD(1V8).8_117") (pintype "power_in"))
      (node (ref "U6") (pin "126") (pinfunction "VDD(1V8).9_126") (pintype "power_in"))
      (node (ref "U6") (pin "139") (pinfunction "VDD(1V8).10_139") (pintype "power_in"))
      (node (ref "U6") (pin "146") (pinfunction "VDD(1V8).11_146") (pintype "power_in"))
      (node (ref "U6") (pin "15") (pinfunction "VDD(1V8).2_15") (pintype "power_in"))
      (node (ref "U6") (pin "154") (pinfunction "VDD(1V8).12_154") (pintype "power_in"))
      (node (ref "U6") (pin "167") (pinfunction "VDD(1V8).12_167") (pintype "power_in"))
      (node (ref "U6") (pin "23") (pinfunction "VDD(1V8).3_23") (pintype "power_in"))
      (node (ref "U6") (pin "29") (pinfunction "VDD(1V8).4_29") (pintype "power_in"))
      (node (ref "U6") (pin "31") (pinfunction "VDD1A18_31") (pintype "power_in"))
      (node (ref "U6") (pin "4") (pinfunction "VDD(1V8).1_4") (pintype "power_in"))
      (node (ref "U6") (pin "59") (pinfunction "VDD2A18_59") (pintype "power_in"))
      (node (ref "U6") (pin "61") (pinfunction "VDD(1V8).5_61") (pintype "power_in"))
    )
    (net (code "133") (name "3.3VD") (class "Default")
      (node (ref "C29") (pin "1") (pinfunction "A_1") (pintype "passive"))
      (node (ref "C30") (pin "1") (pinfunction "A_1") (pintype "passive"))
      (node (ref "C31") (pin "1") (pinfunction "A_1") (pintype "passive"))
      (node (ref "C32") (pin "1") (pinfunction "A_1") (pintype "passive"))
      (node (ref "C33") (pin "1") (pinfunction "A_1") (pintype "passive"))
      (node (ref "C34") (pin "1") (pinfunction "A_1") (pintype "passive"))
      (node (ref "C35") (pin "1") (pinfunction "A_1") (pintype "passive"))
      (node (ref "C36") (pin "1") (pinfunction "A_1") (pintype "passive"))
      (node (ref "C37") (pin "1") (pinfunction "A_1") (pintype "passive"))
      (node (ref "C38") (pin "1") (pinfunction "A_1") (pintype "passive"))
      (node (ref "C39") (pin "1") (pinfunction "A_1") (pintype "passive"))
      (node (ref "C40") (pin "1") (pinfunction "A_1") (pintype "passive"))
      (node (ref "C55") (pin "1") (pinfunction "A_1") (pintype "passive"))
      (node (ref "DSP JTAG") (pin "5") (pinfunction "PD_3.3V_5") (pintype "passive"))
      (node (ref "OSC1") (pin "1") (pinfunction "OE_1") (pintype "input"))
      (node (ref "OSC1") (pin "4") (pinfunction "VCC_4") (pintype "power_in"))
      (node (ref "R11") (pin "1") (pinfunction "A_1") (pintype "passive"))
      (node (ref "R12") (pin "1") (pinfunction "A_1") (pintype "passive"))
      (node (ref "R14") (pin "1") (pinfunction "A_1") (pintype "passive"))
      (node (ref "R18") (pin "5") (pinfunction "5_5") (pintype "passive"))
      (node (ref "R18") (pin "6") (pinfunction "6_6") (pintype "passive"))
      (node (ref "R18") (pin "7") (pinfunction "7_7") (pintype "passive"))
      (node (ref "R18") (pin "8") (pinfunction "8_8") (pintype "passive"))
      (node (ref "R25") (pin "1") (pinfunction "A_1") (pintype "passive"))
      (node (ref "R26") (pin "1") (pinfunction "A_1") (pintype "passive"))
      (node (ref "R44") (pin "1") (pinfunction "A_1") (pintype "passive"))
      (node (ref "R45") (pin "1") (pinfunction "A_1") (pintype "passive"))
      (node (ref "R6") (pin "2") (pinfunction "B_2") (pintype "passive"))
      (node (ref "R9") (pin "1") (pinfunction "A_1") (pintype "passive"))
      (node (ref "U3") (pin "16") (pinfunction "VDD_16") (pintype "passive"))
      (node (ref "U6") (pin "107") (pinfunction "VDDIO(3V3).4_107") (pintype "power_in"))
      (node (ref "U6") (pin "121") (pinfunction "VDDIO(3V3).5_121") (pintype "power_in"))
      (node (ref "U6") (pin "143") (pinfunction "VDDIO(3V3).6_143") (pintype "power_in"))
      (node (ref "U6") (pin "159") (pinfunction "VDDIO(3V3).7_159") (pintype "power_in"))
      (node (ref "U6") (pin "170") (pinfunction "VDDIO(3V3).8_170") (pintype "power_in"))
      (node (ref "U6") (pin "34") (pinfunction "VDDA2(A3V3)_34") (pintype "power_in"))
      (node (ref "U6") (pin "45") (pinfunction "VDDAIO(A3V3)_45") (pintype "power_in"))
      (node (ref "U6") (pin "71") (pinfunction "VDDIO(3V3).2_71") (pintype "power_in"))
      (node (ref "U6") (pin "84") (pinfunction "VDD3VFL.1_84") (pintype "power_in"))
      (node (ref "U6") (pin "9") (pinfunction "VDDIO(3V3).1_9") (pintype "power_in"))
      (node (ref "U6") (pin "93") (pinfunction "VDDIO(3V3).3_93") (pintype "power_in"))
      (node (ref "U8") (pin "3") (pinfunction "OUT_3") (pintype "passive"))
    )
    (net (code "134") (name "5VD") (class "Default")
      (node (ref "R13") (pin "1") (pinfunction "A_1") (pintype "passive"))
      (node (ref "U7") (pin "13") (pinfunction "VCC_13") (pintype "passive"))
      (node (ref "U8") (pin "4") (pinfunction "IN_4") (pintype "passive"))
    )
    (net (code "135") (name "DGND") (class "Default")
      (node (ref "C11") (pin "2") (pinfunction "B_2") (pintype "passive"))
      (node (ref "C12") (pin "2") (pinfunction "B_2") (pintype "passive"))
      (node (ref "C13") (pin "2") (pinfunction "B_2") (pintype "passive"))
      (node (ref "C14") (pin "2") (pinfunction "B_2") (pintype "passive"))
      (node (ref "C15") (pin "2") (pinfunction "B_2") (pintype "passive"))
      (node (ref "C16") (pin "2") (pinfunction "B_2") (pintype "passive"))
      (node (ref "C17") (pin "2") (pinfunction "B_2") (pintype "passive"))
      (node (ref "C18") (pin "2") (pinfunction "B_2") (pintype "passive"))
      (node (ref "C19") (pin "2") (pinfunction "B_2") (pintype "passive"))
      (node (ref "C20") (pin "2") (pinfunction "B_2") (pintype "passive"))
      (node (ref "C21") (pin "2") (pinfunction "B_2") (pintype "passive"))
      (node (ref "C22") (pin "2") (pinfunction "B_2") (pintype "passive"))
      (node (ref "C24") (pin "1") (pinfunction "A_1") (pintype "passive"))
      (node (ref "C25") (pin "1") (pinfunction "A_1") (pintype "passive"))
      (node (ref "C29") (pin "2") (pinfunction "B_2") (pintype "passive"))
      (node (ref "C30") (pin "2") (pinfunction "B_2") (pintype "passive"))
      (node (ref "C31") (pin "2") (pinfunction "B_2") (pintype "passive"))
      (node (ref "C32") (pin "2") (pinfunction "B_2") (pintype "passive"))
      (node (ref "C33") (pin "2") (pinfunction "B_2") (pintype "passive"))
      (node (ref "C34") (pin "2") (pinfunction "B_2") (pintype "passive"))
      (node (ref "C35") (pin "2") (pinfunction "B_2") (pintype "passive"))
      (node (ref "C36") (pin "2") (pinfunction "B_2") (pintype "passive"))
      (node (ref "C37") (pin "2") (pinfunction "B_2") (pintype "passive"))
      (node (ref "C38") (pin "2") (pinfunction "B_2") (pintype "passive"))
      (node (ref "C39") (pin "2") (pinfunction "B_2") (pintype "passive"))
      (node (ref "C40") (pin "2") (pinfunction "B_2") (pintype "passive"))
      (node (ref "C55") (pin "2") (pinfunction "B_2") (pintype "passive"))
      (node (ref "C56") (pin "1") (pinfunction "A_1") (pintype "passive"))
      (node (ref "C59") (pin "2") (pinfunction "B_2") (pintype "passive"))
      (node (ref "C9") (pin "2") (pinfunction "B_2") (pintype "passive"))
      (node (ref "D10") (pin "C") (pinfunction "C_C") (pintype "passive"))
      (node (ref "D2") (pin "1") (pinfunction "K_1") (pintype "passive"))
      (node (ref "D9") (pin "C") (pinfunction "C_C") (pintype "passive"))
      (node (ref "DGND") (pin "1") (pintype "passive"))
      (node (ref "DSP JTAG") (pin "10") (pinfunction "DGND_10") (pintype "passive"))
      (node (ref "DSP JTAG") (pin "12") (pinfunction "DGND_12") (pintype "passive"))
      (node (ref "DSP JTAG") (pin "4") (pinfunction "DGND_4") (pintype "passive"))
      (node (ref "DSP JTAG") (pin "6") (pinfunction "NC_6") (pintype "passive"))
      (node (ref "DSP JTAG") (pin "8") (pinfunction "DGND_8") (pintype "passive"))
      (node (ref "OSC1") (pin "2") (pinfunction "DGND_2") (pintype "power_in"))
      (node (ref "P2") (pin "5") (pinfunction "DGND_5") (pintype "passive"))
      (node (ref "P2") (pin "SHD") (pinfunction "SHD_SHD") (pintype "passive"))
      (node (ref "R19") (pin "1") (pinfunction "A_1") (pintype "passive"))
      (node (ref "R20") (pin "2") (pinfunction "B_2") (pintype "passive"))
      (node (ref "R28") (pin "2") (pinfunction "B_2") (pintype "passive"))
      (node (ref "R43") (pin "1") (pinfunction "A_1") (pintype "passive"))
      (node (ref "S1") (pin "1") (pinfunction "A_1") (pintype "passive"))
      (node (ref "S1") (pin "2") (pinfunction "A'_2") (pintype "passive"))
      (node (ref "SPI") (pin "5") (pinfunction "5_5") (pintype "passive"))
      (node (ref "U3") (pin "9") (pinfunction "DGND_9") (pintype "passive"))
      (node (ref "U6") (pin "103") (pinfunction "VSS.10_103") (pintype "power_in"))
      (node (ref "U6") (pin "104") (pinfunction "X1_104") (pintype "input"))
      (node (ref "U6") (pin "106") (pinfunction "VSS.11_106") (pintype "power_in"))
      (node (ref "U6") (pin "108") (pinfunction "VSS.12_108") (pintype "power_in"))
      (node (ref "U6") (pin "118") (pinfunction "VSS.13_118") (pintype "power_in"))
      (node (ref "U6") (pin "120") (pinfunction "VSS.14_120") (pintype "power_in"))
      (node (ref "U6") (pin "125") (pinfunction "VSS.15_125") (pintype "power_in"))
      (node (ref "U6") (pin "14") (pinfunction "VSS.3_14") (pintype "power_in"))
      (node (ref "U6") (pin "140") (pinfunction "VSS.16_140") (pintype "power_in"))
      (node (ref "U6") (pin "144") (pinfunction "VSS.17_144") (pintype "power_in"))
      (node (ref "U6") (pin "147") (pinfunction "VSS.18_147") (pintype "power_in"))
      (node (ref "U6") (pin "155") (pinfunction "VSS.19_155") (pintype "power_in"))
      (node (ref "U6") (pin "160") (pinfunction "VSS.19_160") (pintype "power_in"))
      (node (ref "U6") (pin "166") (pinfunction "VSS.20_166") (pintype "power_in"))
      (node (ref "U6") (pin "171") (pinfunction "VSS.21_171") (pintype "power_in"))
      (node (ref "U6") (pin "22") (pinfunction "VSS.4_22") (pintype "power_in"))
      (node (ref "U6") (pin "3") (pinfunction "VSS.1_3") (pintype "power_in"))
      (node (ref "U6") (pin "30") (pinfunction "VSS.5_30") (pintype "power_in"))
      (node (ref "U6") (pin "32") (pinfunction "VSS1ADGND_32") (pintype "power_in"))
      (node (ref "U6") (pin "33") (pinfunction "VSSA2(ADGND)_33") (pintype "power_in"))
      (node (ref "U6") (pin "35") (pinfunction "ADCINA7_35") (pintype "bidirectional"))
      (node (ref "U6") (pin "36") (pinfunction "ADCINA6_36") (pintype "bidirectional"))
      (node (ref "U6") (pin "37") (pinfunction "ADCINA5_37") (pintype "bidirectional"))
      (node (ref "U6") (pin "38") (pinfunction "ADCINA4_38") (pintype "bidirectional"))
      (node (ref "U6") (pin "39") (pinfunction "ADCINA3_39") (pintype "bidirectional"))
      (node (ref "U6") (pin "40") (pinfunction "ADCINA2_40") (pintype "bidirectional"))
      (node (ref "U6") (pin "41") (pinfunction "ADCINA1_41") (pintype "bidirectional"))
      (node (ref "U6") (pin "42") (pinfunction "ADCINA0_42") (pintype "bidirectional"))
      (node (ref "U6") (pin "43") (pinfunction "ADCLO_43") (pintype "bidirectional"))
      (node (ref "U6") (pin "44") (pinfunction "VSSAIO(ADGND)_44") (pintype "power_in"))
      (node (ref "U6") (pin "46") (pinfunction "ADCINB0_46") (pintype "bidirectional"))
      (node (ref "U6") (pin "47") (pinfunction "ADCINB1_47") (pintype "bidirectional"))
      (node (ref "U6") (pin "48") (pinfunction "ADCINB2_48") (pintype "bidirectional"))
      (node (ref "U6") (pin "49") (pinfunction "ADCINB3_49") (pintype "bidirectional"))
      (node (ref "U6") (pin "50") (pinfunction "ADCINB4_50") (pintype "bidirectional"))
      (node (ref "U6") (pin "51") (pinfunction "ADCINB5_51") (pintype "bidirectional"))
      (node (ref "U6") (pin "52") (pinfunction "ADCINB6_52") (pintype "bidirectional"))
      (node (ref "U6") (pin "53") (pinfunction "ADCINB7_53") (pintype "bidirectional"))
      (node (ref "U6") (pin "54") (pinfunction "ADCREFIN_54") (pintype "bidirectional"))
      (node (ref "U6") (pin "58") (pinfunction "VSS2ADGND_58") (pintype "power_in"))
      (node (ref "U6") (pin "60") (pinfunction "VSS.6_60") (pintype "power_in"))
      (node (ref "U6") (pin "70") (pinfunction "VSS.7_70") (pintype "power_in"))
      (node (ref "U6") (pin "8") (pinfunction "VSS.2_8") (pintype "power_in"))
      (node (ref "U6") (pin "83") (pinfunction "VSS.8_83") (pintype "power_in"))
      (node (ref "U6") (pin "92") (pinfunction "VSS.9_92") (pintype "power_in"))
      (node (ref "U7") (pin "14") (pinfunction "DGND_14") (pintype "passive"))
      (node (ref "U7") (pin "4") (pinfunction "DGND_4") (pintype "passive"))
      (node (ref "U8") (pin "5") (pinfunction "DGND_5") (pintype "passive"))
    )
    (net (code "136") (name "Net-(C24-B)") (class "Default")
      (node (ref "C24") (pin "2") (pinfunction "B_2") (pintype "passive"))
      (node (ref "U6") (pin "56") (pinfunction "ADCREFP_56") (pintype "output"))
    )
    (net (code "137") (name "Net-(C25-B)") (class "Default")
      (node (ref "C25") (pin "2") (pinfunction "B_2") (pintype "passive"))
      (node (ref "U6") (pin "55") (pinfunction "ADCREFM_55") (pintype "output"))
    )
    (net (code "138") (name "Net-(C56-B)") (class "Default")
      (node (ref "C56") (pin "2") (pinfunction "B_2") (pintype "passive"))
      (node (ref "P2") (pin "2") (pinfunction "D-_2") (pintype "passive"))
      (node (ref "R20") (pin "1") (pinfunction "A_1") (pintype "passive"))
      (node (ref "R40") (pin "2") (pinfunction "B_2") (pintype "passive"))
    )
    (net (code "139") (name "Net-(C59-A)") (class "Default")
      (node (ref "C59") (pin "1") (pinfunction "A_1") (pintype "passive"))
      (node (ref "P2") (pin "3") (pinfunction "D+_3") (pintype "passive"))
      (node (ref "R41") (pin "2") (pinfunction "B_2") (pintype "passive"))
      (node (ref "R42") (pin "2") (pinfunction "B_2") (pintype "passive"))
    )
    (net (code "140") (name "Net-(D2-A)") (class "Default")
      (node (ref "D2") (pin "2") (pinfunction "A_2") (pintype "passive"))
      (node (ref "R34") (pin "1") (pinfunction "A_1") (pintype "passive"))
    )
    (net (code "141") (name "Net-(D4-A)") (class "Default")
      (node (ref "D4") (pin "2") (pinfunction "A_2") (pintype "passive"))
      (node (ref "R12") (pin "2") (pinfunction "B_2") (pintype "passive"))
    )
    (net (code "142") (name "Net-(P2-VBUS)") (class "Default")
      (node (ref "P2") (pin "1") (pinfunction "VBUS_1") (pintype "passive"))
      (node (ref "R27") (pin "1") (pinfunction "A_1") (pintype "passive"))
    )
    (net (code "143") (name "Net-(R9-B)") (class "Default")
      (node (ref "R9") (pin "2") (pinfunction "B_2") (pintype "passive"))
      (node (ref "U3") (pin "10") (pinfunction "~{SHDN}_10") (pintype "passive"))
    )
    (net (code "144") (name "Net-(R13-B)") (class "Default")
      (node (ref "R13") (pin "2") (pinfunction "B_2") (pintype "passive"))
      (node (ref "U8") (pin "1") (pinfunction "EN_1") (pintype "passive"))
    )
    (net (code "145") (name "Net-(R14-B)") (class "Default")
      (node (ref "D9") (pin "A") (pinfunction "A_A") (pintype "passive"))
      (node (ref "R14") (pin "2") (pinfunction "B_2") (pintype "passive"))
    )
    (net (code "146") (name "Net-(R24-A)") (class "Default")
      (node (ref "D10") (pin "A") (pinfunction "A_A") (pintype "passive"))
      (node (ref "R24") (pin "1") (pinfunction "A_1") (pintype "passive"))
    )
    (net (code "147") (name "Net-(R28-A)") (class "Default")
      (node (ref "R28") (pin "1") (pinfunction "A_1") (pintype "passive"))
      (node (ref "U6") (pin "57") (pinfunction "ADCRESEXT_57") (pintype "output"))
    )
    (net (code "148") (name "Net-(R44-B)") (class "Default")
      (node (ref "R44") (pin "2") (pinfunction "B_2") (pintype "passive"))
      (node (ref "U7") (pin "7") (pinfunction "~{INT}_7") (pintype "passive"))
    )
    (net (code "149") (name "Net-(R45-B)") (class "Default")
      (node (ref "R45") (pin "2") (pinfunction "B_2") (pintype "passive"))
      (node (ref "U7") (pin "6") (pinfunction "SUSPEND_6") (pintype "passive"))
    )
    (net (code "150") (name "unconnected-(P2-ID-Pad4)") (class "Default")
      (node (ref "P2") (pin "4") (pinfunction "ID_4") (pintype "passive"))
    )
    (net (code "151") (name "unconnected-(U6-(NC)_TEST1-Pad81)") (class "Default")
      (node (ref "U6") (pin "81") (pinfunction "(NC)_TEST1_81") (pintype "tri_state"))
    )
    (net (code "152") (name "unconnected-(U6-(NC)_TEST2-Pad82)") (class "Default")
      (node (ref "U6") (pin "82") (pinfunction "(NC)_TEST2_82") (pintype "tri_state"))
    )
    (net (code "153") (name "unconnected-(U6-GPIO24{slash}ECAP1{slash}EQEP2A{slash}MDXB-Pad68)") (class "Default")
      (node (ref "U6") (pin "68") (pinfunction "GPIO24/ECAP1/EQEP2A/MDXB_68") (pintype "bidirectional"))
    )
    (net (code "154") (name "unconnected-(U6-GPIO29{slash}SCITXDA{slash}XA19-Pad2)") (class "Default")
      (node (ref "U6") (pin "2") (pinfunction "GPIO29/SCITXDA/XA19_2") (pintype "output"))
    )
    (net (code "155") (name "unconnected-(U6-GPIO30{slash}CANRXA{slash}XA18-Pad1)") (class "Default")
      (node (ref "U6") (pin "1") (pinfunction "GPIO30/CANRXA/XA18_1") (pintype "output"))
    )
    (net (code "156") (name "unconnected-(U6-GPIO31{slash}CANTXA{slash}XA17-Pad176)") (class "Default")
      (node (ref "U6") (pin "176") (pinfunction "GPIO31/CANTXA/XA17_176") (pintype "output"))
    )
    (net (code "157") (name "unconnected-(U6-GPIO39{slash}XA16-Pad175)") (class "Default")
      (node (ref "U6") (pin "175") (pinfunction "GPIO39/XA16_175") (pintype "output"))
    )
    (net (code "158") (name "unconnected-(U6-X2-Pad102)") (class "Default")
      (node (ref "U6") (pin "102") (pinfunction "X2_102") (pintype "tri_state"))
    )
    (net (code "159") (name "unconnected-(U6-XCLKOUT-Pad138)") (class "Default")
      (node (ref "U6") (pin "138") (pinfunction "XCLKOUT_138") (pintype "output"))
    )
    (net (code "160") (name "unconnected-(U7-~{BCD}-Pad1)") (class "Default")
      (node (ref "U7") (pin "1") (pinfunction "~{BCD}_1") (pintype "passive"))
    )
    (net (code "161") (name "unconnected-(U8-NC-Pad2)") (class "Default")
      (node (ref "U8") (pin "2") (pinfunction "NC_2") (pintype "passive"))
    )
  )
)
